# main.net
KiCad netlist of a schematic drawn in EAGLE
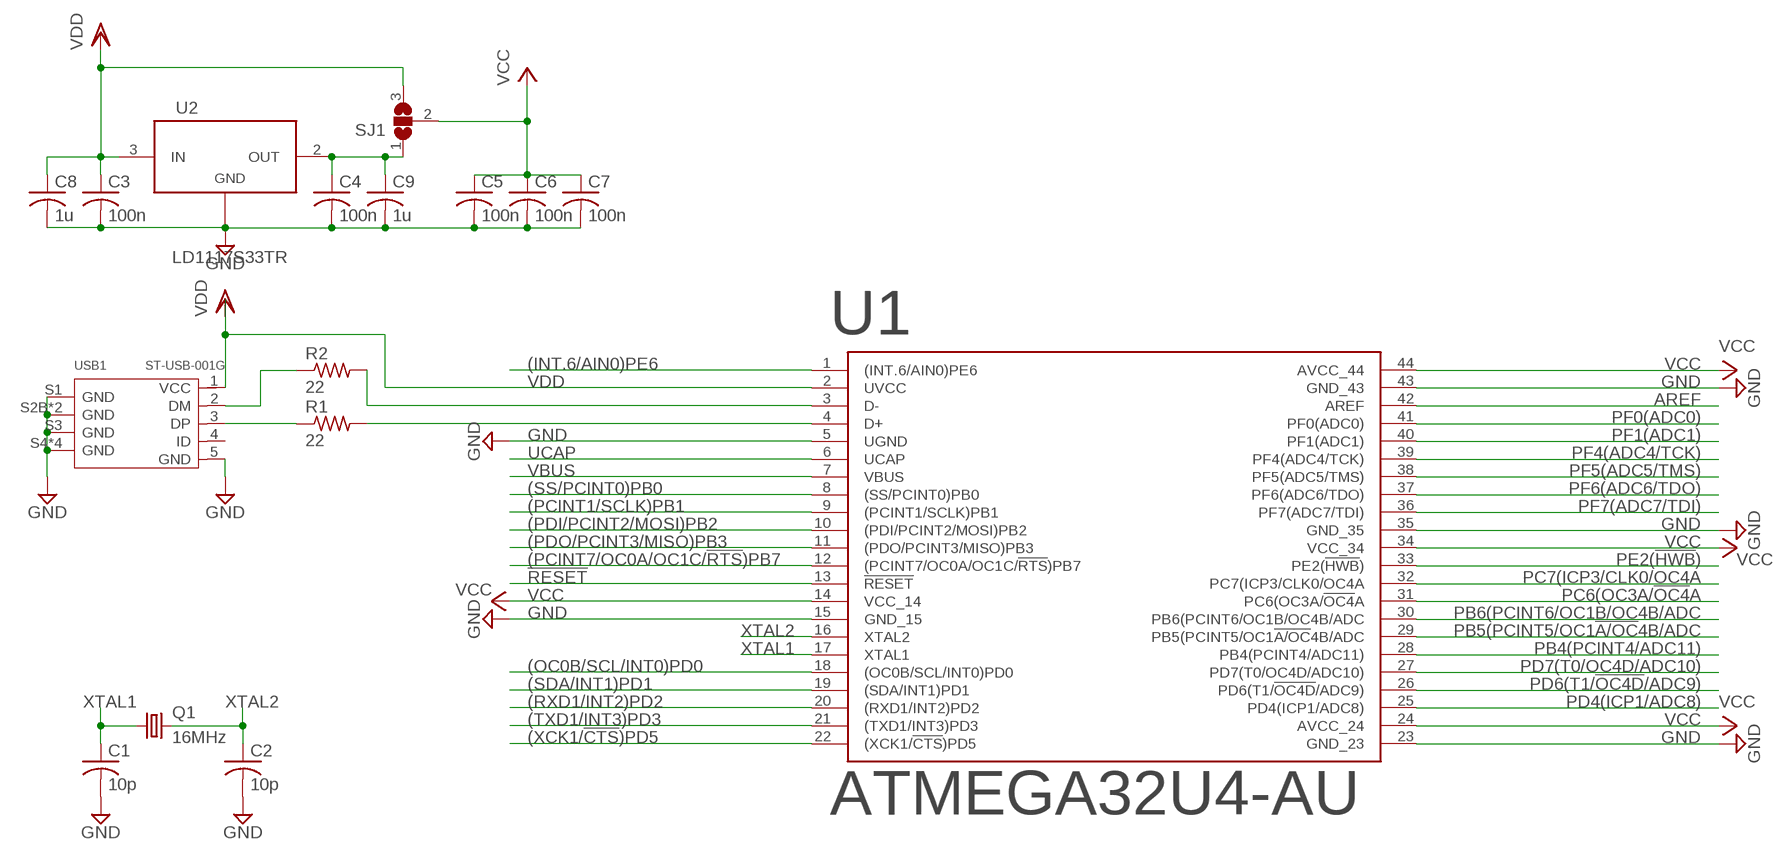
[diagram p0: schematic, sheet 1]

(export (version "E")
  (design (tool "Eeschema 10.0.6"))
  (components
    (comp (ref "C1")
      (value "10p")
      (footprint "eagle-import:C0603")
      (libsource (lib "eagle-import") (part "C-USC0603"))
    )
    (comp (ref "C2")
      (value "10p")
      (footprint "eagle-import:C0603")
      (libsource (lib "eagle-import") (part "C-USC0603"))
    )
    (comp (ref "C3")
      (value "100n")
      (footprint "eagle-import:C0603")
      (libsource (lib "eagle-import") (part "C-USC0603"))
    )
    (comp (ref "C4")
      (value "100n")
      (footprint "eagle-import:C0603")
      (libsource (lib "eagle-import") (part "C-USC0603"))
    )
    (comp (ref "C5")
      (value "100n")
      (footprint "eagle-import:C0603")
      (libsource (lib "eagle-import") (part "C-USC0603"))
    )
    (comp (ref "C6")
      (value "100n")
      (footprint "eagle-import:C0603")
      (libsource (lib "eagle-import") (part "C-USC0603"))
    )
    (comp (ref "C7")
      (value "100n")
      (footprint "eagle-import:C0603")
      (libsource (lib "eagle-import") (part "C-USC0603"))
    )
    (comp (ref "C8")
      (value "1u")
      (footprint "eagle-import:C0805")
      (libsource (lib "eagle-import") (part "C-USC0805"))
    )
    (comp (ref "C9")
      (value "1u")
      (footprint "eagle-import:C0805")
      (libsource (lib "eagle-import") (part "C-USC0805"))
    )
    (comp (ref "Q1")
      (value "16MHz")
      (footprint "eagle-import:HC49U-V")
      (libsource (lib "eagle-import") (part "CRYSTALHC49U-V"))
    )
    (comp (ref "R1")
      (value "22")
      (footprint "eagle-import:R0603")
      (libsource (lib "eagle-import") (part "R-US_R0603"))
    )
    (comp (ref "R2")
      (value "22")
      (footprint "eagle-import:R0603")
      (libsource (lib "eagle-import") (part "R-US_R0603"))
    )
    (comp (ref "SJ1")
      (value "SJ2W")
      (footprint "eagle-import:SJ_2")
      (libsource (lib "eagle-import") (part "SJ2W"))
    )
    (comp (ref "U1")
      (value "ATMEGA32U4-AU")
      (footprint "eagle-import:44-TQFP")
      (fields
        (field (name "DIGIKEY_PART_NUMBER") "ATMEGA32U4-AU-ND")
        (field (name "MANUFACTURER") "Microchip Technology")
        (field (name "CREATED_BY") "PCBLayout.com")
      )
      (libsource (lib "eagle-import") (part "ATMEGA32U4-AU"))
    )
    (comp (ref "U2")
      (value "LD1117S33TR")
      (footprint "eagle-import:SOT-223")
      (fields
        (field (name "DIGIKEY_PART_NUMBER") "497-1242-2-ND")
        (field (name "MANUFACTURER") "STMicroelectronics")
        (field (name "CREATED_BY") "PCBLayout.com")
      )
      (libsource (lib "eagle-import") (part "LD1117S33TR"))
    )
    (comp (ref "USB1")
      (value "ST-USB-001G")
      (footprint "eagle-import:MICRO-USB5+4P-SMD-0.65-B")
      (libsource (lib "eagle-import") (part "MICRO-USB-SMD-B-WITHOUT-POST-W/P(ST-USB-001G)"))
    )
  )
  (nets
    (net (code "1") (name "/(INT.6{slash}AIN0)PE6") (class "Default")
      (node (ref "U1") (pin "1") (pinfunction "(INT.6/AIN0)PE6_1") (pintype "bidirectional"))
    )
    (net (code "2") (name "/(OC0B{slash}SCL{slash}INT0)PD0") (class "Default")
      (node (ref "U1") (pin "18") (pinfunction "(OC0B/SCL/INT0)PD0_18") (pintype "bidirectional"))
    )
    (net (code "3") (name "/(PCINT1{slash}SCLK)PB1") (class "Default")
      (node (ref "U1") (pin "9") (pinfunction "(PCINT1/SCLK)PB1_9") (pintype "bidirectional"))
    )
    (net (code "4") (name "/(PCINT7{slash}OC0A{slash}OC1C{slash}~{RTS})PB7") (class "Default")
      (node (ref "U1") (pin "12") (pinfunction "(PCINT7/OC0A/OC1C/~{RTS})PB7_12") (pintype "bidirectional"))
    )
    (net (code "5") (name "/(PDI{slash}PCINT2{slash}MOSI)PB2") (class "Default")
      (node (ref "U1") (pin "10") (pinfunction "(PDI/PCINT2/MOSI)PB2_10") (pintype "bidirectional"))
    )
    (net (code "6") (name "/(PDO{slash}PCINT3{slash}MISO)PB3") (class "Default")
      (node (ref "U1") (pin "11") (pinfunction "(PDO/PCINT3/MISO)PB3_11") (pintype "bidirectional"))
    )
    (net (code "7") (name "/(RXD1{slash}INT2)PD2") (class "Default")
      (node (ref "U1") (pin "20") (pinfunction "(RXD1/INT2)PD2_20") (pintype "bidirectional"))
    )
    (net (code "8") (name "/(SDA{slash}INT1)PD1") (class "Default")
      (node (ref "U1") (pin "19") (pinfunction "(SDA/INT1)PD1_19") (pintype "bidirectional"))
    )
    (net (code "9") (name "/(SS{slash}PCINT0)PB0") (class "Default")
      (node (ref "U1") (pin "8") (pinfunction "(SS/PCINT0)PB0_8") (pintype "bidirectional"))
    )
    (net (code "10") (name "/(TXD1{slash}INT3)PD3") (class "Default")
      (node (ref "U1") (pin "21") (pinfunction "(TXD1/INT3)PD3_21") (pintype "bidirectional"))
    )
    (net (code "11") (name "/(XCK1{slash}~{CTS})PD5") (class "Default")
      (node (ref "U1") (pin "22") (pinfunction "(XCK1/~{CTS})PD5_22") (pintype "bidirectional"))
    )
    (net (code "12") (name "/AREF") (class "Default")
      (node (ref "U1") (pin "42") (pinfunction "AREF_42") (pintype "input"))
    )
    (net (code "13") (name "/PB4(PCINT4{slash}ADC11)") (class "Default")
      (node (ref "U1") (pin "28") (pinfunction "PB4(PCINT4/ADC11)_28") (pintype "bidirectional"))
    )
    (net (code "14") (name "/PB5(PCINT5{slash}OC1~{A{slash}OC}4B{slash}ADC") (class "Default")
      (node (ref "U1") (pin "29") (pinfunction "PB5(PCINT5/OC1~{A/OC}4B/ADC_29") (pintype "bidirectional"))
    )
    (net (code "15") (name "/PB6(PCINT6{slash}OC1B{slash}OC4B{slash}ADC") (class "Default")
      (node (ref "U1") (pin "30") (pinfunction "PB6(PCINT6/OC1B/OC4B/ADC_30") (pintype "bidirectional"))
    )
    (net (code "16") (name "/PC6(OC3A{slash}~{OC4}A") (class "Default")
      (node (ref "U1") (pin "31") (pinfunction "PC6(OC3A/~{OC4}A_31") (pintype "bidirectional"))
    )
    (net (code "17") (name "/PC7(ICP3{slash}CLK0{slash}OC4A") (class "Default")
      (node (ref "U1") (pin "32") (pinfunction "PC7(ICP3/CLK0/OC4A_32") (pintype "bidirectional"))
    )
    (net (code "18") (name "/PD4(ICP1{slash}ADC8)") (class "Default")
      (node (ref "U1") (pin "25") (pinfunction "PD4(ICP1/ADC8)_25") (pintype "bidirectional"))
    )
    (net (code "19") (name "/PD6(T1{slash}~{OC4D}{slash}ADC9)") (class "Default")
      (node (ref "U1") (pin "26") (pinfunction "PD6(T1/~{OC4D}/ADC9)_26") (pintype "bidirectional"))
    )
    (net (code "20") (name "/PD7(T0{slash}OC4D{slash}ADC10)") (class "Default")
      (node (ref "U1") (pin "27") (pinfunction "PD7(T0/OC4D/ADC10)_27") (pintype "bidirectional"))
    )
    (net (code "21") (name "/PE2(~{HWB})") (class "Default")
      (node (ref "U1") (pin "33") (pinfunction "PE2(~{HWB})_33") (pintype "bidirectional"))
    )
    (net (code "22") (name "/PF0(ADC0)") (class "Default")
      (node (ref "U1") (pin "41") (pinfunction "PF0(ADC0)_41") (pintype "bidirectional"))
    )
    (net (code "23") (name "/PF1(ADC1)") (class "Default")
      (node (ref "U1") (pin "40") (pinfunction "PF1(ADC1)_40") (pintype "bidirectional"))
    )
    (net (code "24") (name "/PF4(ADC4{slash}TCK)") (class "Default")
      (node (ref "U1") (pin "39") (pinfunction "PF4(ADC4/TCK)_39") (pintype "bidirectional"))
    )
    (net (code "25") (name "/PF5(ADC5{slash}TMS)") (class "Default")
      (node (ref "U1") (pin "38") (pinfunction "PF5(ADC5/TMS)_38") (pintype "bidirectional"))
    )
    (net (code "26") (name "/PF6(ADC6{slash}TDO)") (class "Default")
      (node (ref "U1") (pin "37") (pinfunction "PF6(ADC6/TDO)_37") (pintype "bidirectional"))
    )
    (net (code "27") (name "/PF7(ADC7{slash}TDI)") (class "Default")
      (node (ref "U1") (pin "36") (pinfunction "PF7(ADC7/TDI)_36") (pintype "bidirectional"))
    )
    (net (code "28") (name "/UCAP") (class "Default")
      (node (ref "U1") (pin "6") (pinfunction "UCAP_6") (pintype "power_in"))
    )
    (net (code "29") (name "/VBUS") (class "Default")
      (node (ref "U1") (pin "7") (pinfunction "VBUS_7") (pintype "input"))
    )
    (net (code "30") (name "/XTAL1") (class "Default")
      (node (ref "C1") (pin "1") (pinfunction "1_1") (pintype "passive"))
      (node (ref "Q1") (pin "1") (pinfunction "1_1") (pintype "passive"))
      (node (ref "U1") (pin "17") (pinfunction "XTAL1_17") (pintype "input"))
    )
    (net (code "31") (name "/XTAL2") (class "Default")
      (node (ref "C2") (pin "1") (pinfunction "1_1") (pintype "passive"))
      (node (ref "Q1") (pin "2") (pinfunction "2_2") (pintype "passive"))
      (node (ref "U1") (pin "16") (pinfunction "XTAL2_16") (pintype "output"))
    )
    (net (code "32") (name "/~{RESET}") (class "Default")
      (node (ref "U1") (pin "13") (pinfunction "~{RESET}_13") (pintype "input"))
    )
    (net (code "33") (name "GND") (class "Default")
      (node (ref "C1") (pin "2") (pinfunction "2_2") (pintype "passive"))
      (node (ref "C2") (pin "2") (pinfunction "2_2") (pintype "passive"))
      (node (ref "C3") (pin "2") (pinfunction "2_2") (pintype "passive"))
      (node (ref "C4") (pin "2") (pinfunction "2_2") (pintype "passive"))
      (node (ref "C5") (pin "2") (pinfunction "2_2") (pintype "passive"))
      (node (ref "C6") (pin "2") (pinfunction "2_2") (pintype "passive"))
      (node (ref "C7") (pin "2") (pinfunction "2_2") (pintype "passive"))
      (node (ref "C8") (pin "2") (pinfunction "2_2") (pintype "passive"))
      (node (ref "C9") (pin "2") (pinfunction "2_2") (pintype "passive"))
      (node (ref "U1") (pin "15") (pinfunction "GND_15_15") (pintype "power_in"))
      (node (ref "U1") (pin "23") (pinfunction "GND_23_23") (pintype "power_in"))
      (node (ref "U1") (pin "35") (pinfunction "GND_35_35") (pintype "power_in"))
      (node (ref "U1") (pin "43") (pinfunction "GND_43_43") (pintype "power_in"))
      (node (ref "U1") (pin "5") (pinfunction "UGND_5") (pintype "power_in"))
      (node (ref "U2") (pin "1") (pinfunction "ADJ/GND_1") (pintype "power_in"))
      (node (ref "USB1") (pin "5") (pinfunction "GND_5") (pintype "bidirectional"))
      (node (ref "USB1") (pin "S1") (pinfunction "GND_S1") (pintype "bidirectional"))
      (node (ref "USB1") (pin "S2B") (pinfunction "GND_S2B") (pintype "bidirectional"))
      (node (ref "USB1") (pin "S2T") (pinfunction "GND_S2T") (pintype "bidirectional"))
      (node (ref "USB1") (pin "S3") (pinfunction "GND_S3") (pintype "bidirectional"))
      (node (ref "USB1") (pin "S4") (pinfunction "GND_S4") (pintype "bidirectional"))
      (node (ref "USB1") (pin "S5B") (pinfunction "GND_S5B") (pintype "bidirectional"))
      (node (ref "USB1") (pin "S5T") (pinfunction "GND_S5T") (pintype "bidirectional"))
      (node (ref "USB1") (pin "S6") (pinfunction "GND_S6") (pintype "bidirectional"))
    )
    (net (code "34") (name "Net-(U1-D+)") (class "Default")
      (node (ref "R1") (pin "2") (pinfunction "2_2") (pintype "passive"))
      (node (ref "U1") (pin "4") (pinfunction "D+_4") (pintype "input"))
    )
    (net (code "35") (name "Net-(U1-D-)") (class "Default")
      (node (ref "R2") (pin "2") (pinfunction "2_2") (pintype "passive"))
      (node (ref "U1") (pin "3") (pinfunction "D-_3") (pintype "input"))
    )
    (net (code "36") (name "Net-(U2-OUT)") (class "Default")
      (node (ref "C4") (pin "1") (pinfunction "1_1") (pintype "passive"))
      (node (ref "C9") (pin "1") (pinfunction "1_1") (pintype "passive"))
      (node (ref "SJ1") (pin "1") (pinfunction "1_1") (pintype "passive"))
      (node (ref "U2") (pin "2") (pinfunction "OUT_2") (pintype "output"))
      (node (ref "U2") (pin "4") (pinfunction "4_4") (pintype "passive"))
    )
    (net (code "37") (name "Net-(USB1-DM)") (class "Default")
      (node (ref "R2") (pin "1") (pinfunction "1_1") (pintype "passive"))
      (node (ref "USB1") (pin "2") (pinfunction "DM_2") (pintype "bidirectional"))
    )
    (net (code "38") (name "Net-(USB1-DP)") (class "Default")
      (node (ref "R1") (pin "1") (pinfunction "1_1") (pintype "passive"))
      (node (ref "USB1") (pin "3") (pinfunction "DP_3") (pintype "bidirectional"))
    )
    (net (code "39") (name "VCC") (class "Default")
      (node (ref "C5") (pin "1") (pinfunction "1_1") (pintype "passive"))
      (node (ref "C6") (pin "1") (pinfunction "1_1") (pintype "passive"))
      (node (ref "C7") (pin "1") (pinfunction "1_1") (pintype "passive"))
      (node (ref "SJ1") (pin "2") (pinfunction "2_2") (pintype "passive"))
      (node (ref "U1") (pin "14") (pinfunction "VCC_14_14") (pintype "power_in"))
      (node (ref "U1") (pin "24") (pinfunction "AVCC_24_24") (pintype "power_in"))
      (node (ref "U1") (pin "34") (pinfunction "VCC_34_34") (pintype "power_in"))
      (node (ref "U1") (pin "44") (pinfunction "AVCC_44_44") (pintype "power_in"))
    )
    (net (code "40") (name "VDD") (class "Default")
      (node (ref "C3") (pin "1") (pinfunction "1_1") (pintype "passive"))
      (node (ref "C8") (pin "1") (pinfunction "1_1") (pintype "passive"))
      (node (ref "SJ1") (pin "3") (pinfunction "3_3") (pintype "passive"))
      (node (ref "U1") (pin "2") (pinfunction "UVCC_2") (pintype "power_in"))
      (node (ref "U2") (pin "3") (pinfunction "IN_3") (pintype "input"))
      (node (ref "USB1") (pin "1") (pinfunction "VCC_1") (pintype "bidirectional"))
    )
    (net (code "41") (name "unconnected-(USB1-ID-Pad4)") (class "Default")
      (node (ref "USB1") (pin "4") (pinfunction "ID_4") (pintype "bidirectional"))
    )
  )
)
